# ACT01_RS232_V3_0.net
KiCad netlist of a schematic drawn in Altium Designer
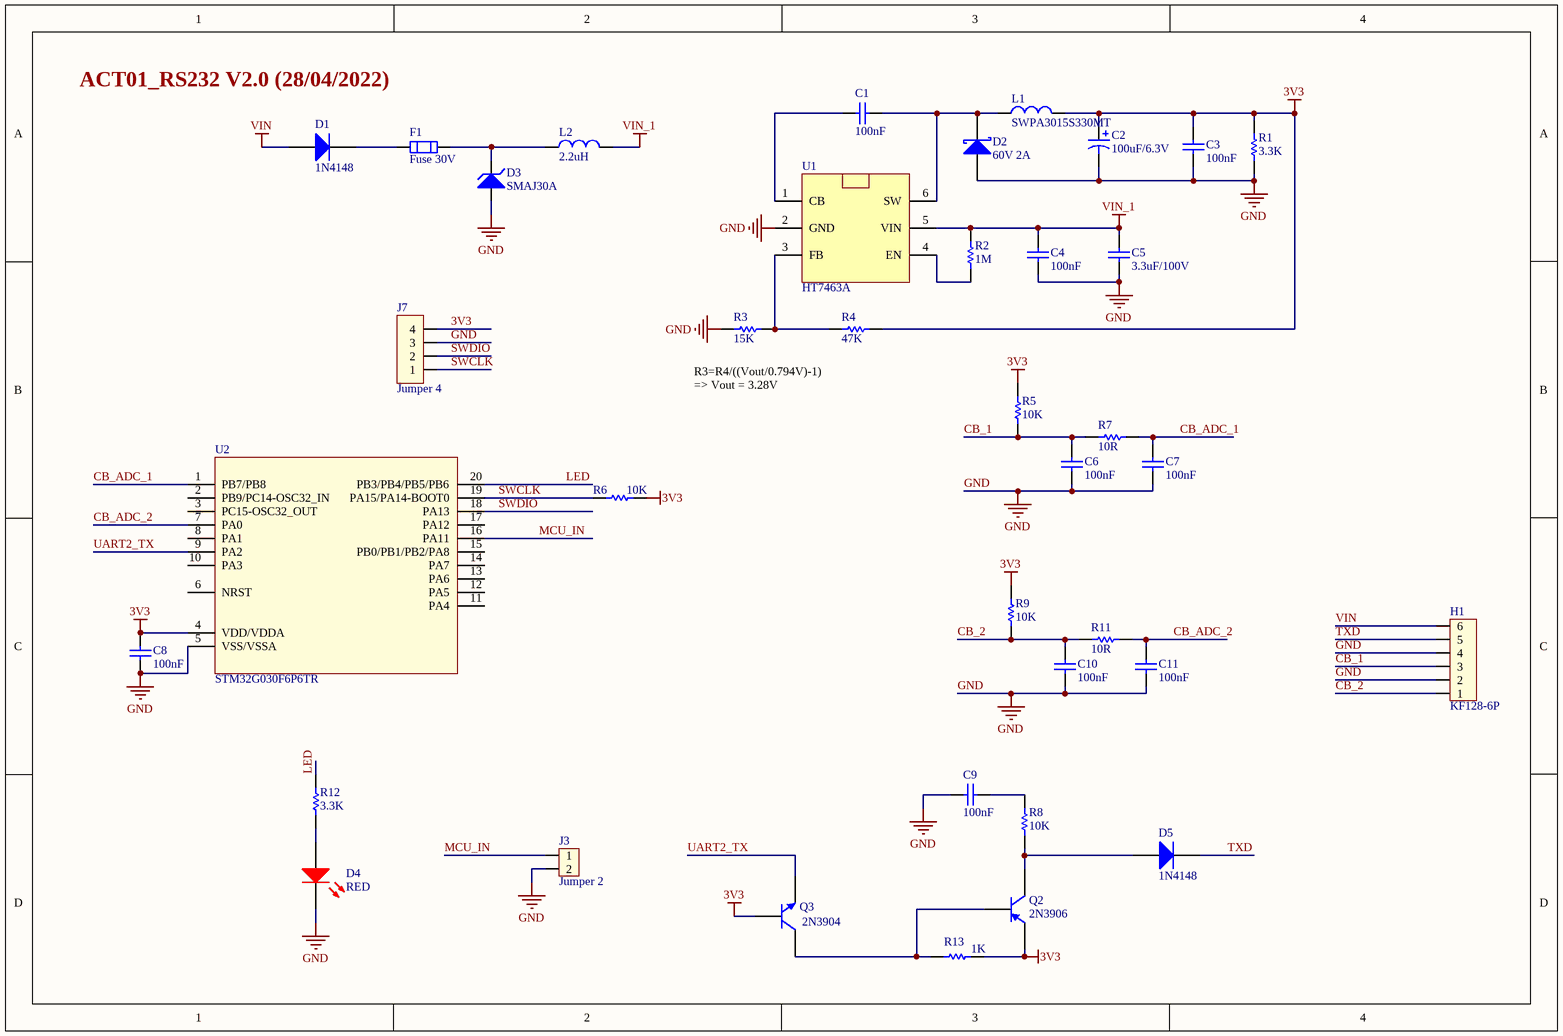
[diagram p0: ACT01_RS232 V3.0.SchDoc]

(export (version "E")
  (design (tool "Eeschema 10.0.6"))
  (components
    (comp (ref "C1")
      (value "100nF")
      (footprint "0603 - C")
      (description "CAP CER 100nF 50V C0G/NP0 0603")
      (fields (field (name "MPN") "CL10C104JB8NNNC") (field (name "MFR") "SAMSUNG"))
      (libsource (lib "Library_Chip1") (part "Cap 0603 100nF"))
    )
    (comp (ref "C2")
      (value "100uF/6.3V")
      (footprint "3528 - TANTALUM")
      (description "CAP TANT 100UF 6.3V 10% 1411")
      (fields (field (name "MPN") "T491B107K006AT") (field (name "MFR") "Kemet"))
      (libsource (lib "Library_Chip1") (part "Cap Tan 3528 100uF/6.3V"))
    )
    (comp (ref "C3")
      (value "100nF")
      (footprint "0603 - C")
      (description "CAP CER 100nF 50V C0G/NP0 0603")
      (fields (field (name "MPN") "CL10C104JB8NNNC") (field (name "MFR") "SAMSUNG"))
      (libsource (lib "Library_Chip1") (part "Cap 0603 100nF"))
    )
    (comp (ref "C4")
      (value "100nF")
      (footprint "0603 - C")
      (description "CAP CER 100nF 50V C0G/NP0 0603")
      (fields (field (name "MPN") "CL10C104JB8NNNC") (field (name "MFR") "SAMSUNG"))
      (libsource (lib "Library_Chip1") (part "Cap 0603 100nF"))
    )
    (comp (ref "C5")
      (value "3.3uF/100V")
      (footprint "1210 - C")
      (description "CAP CER 3.3UF 100V X7S 1210")
      (fields (field (name "MPN") "C3225X7S2A335M200AB") (field (name "MFR") "TDK Corporation"))
      (libsource (lib "Library_Chip1") (part "Cap 1210 3.3uF"))
    )
    (comp (ref "C6")
      (value "100nF")
      (footprint "0603 - C")
      (description "CAP CER 100nF 50V C0G/NP0 0603")
      (fields (field (name "MPN") "CL10C104JB8NNNC") (field (name "MFR") "SAMSUNG"))
      (libsource (lib "Library_Chip1") (part "Cap 0603 100nF"))
    )
    (comp (ref "C7")
      (value "100nF")
      (footprint "0603 - C")
      (description "CAP CER 100nF 50V C0G/NP0 0603")
      (fields (field (name "MPN") "CL10C104JB8NNNC") (field (name "MFR") "SAMSUNG"))
      (libsource (lib "Library_Chip1") (part "Cap 0603 100nF"))
    )
    (comp (ref "C8")
      (value "100nF")
      (footprint "0603 - C")
      (description "CAP CER 100nF 50V C0G/NP0 0603")
      (fields (field (name "MPN") "CL10C104JB8NNNC") (field (name "MFR") "SAMSUNG"))
      (libsource (lib "Library_Chip") (part "Cap 0603 100nF"))
    )
    (comp (ref "C9")
      (value "100nF")
      (footprint "0603 - C")
      (description "CAP CER 100nF 50V C0G/NP0 0603")
      (fields (field (name "MPN") "CL10C104JB8NNNC") (field (name "MFR") "SAMSUNG"))
      (libsource (lib "Library_Chip") (part "Cap 0603 100nF"))
    )
    (comp (ref "C10")
      (value "100nF")
      (footprint "0603 - C")
      (description "CAP CER 100nF 50V C0G/NP0 0603")
      (fields (field (name "MPN") "CL10C104JB8NNNC") (field (name "MFR") "SAMSUNG"))
      (libsource (lib "Library_Chip1") (part "Cap 0603 100nF"))
    )
    (comp (ref "C11")
      (value "100nF")
      (footprint "0603 - C")
      (description "CAP CER 100nF 50V C0G/NP0 0603")
      (fields (field (name "MPN") "CL10C104JB8NNNC") (field (name "MFR") "SAMSUNG"))
      (libsource (lib "Library_Chip1") (part "Cap 0603 100nF"))
    )
    (comp (ref "D1")
      (value "1N4148")
      (footprint "SOD-123")
      (description "DIODE GEN PURP 100V 300MA SOD123")
      (fields (field (name "MPN") "1N4148W-7-F") (field (name "MFR") "DIODES"))
      (libsource (lib "Library_Chip") (part "Diode 1N4148"))
    )
    (comp (ref "D2")
      (value "60V 2A")
      (footprint "SOD-123")
      (description "DIODE SCHOTTKY 60V 2A SOD123W")
      (fields (field (name "MPN") "PMEG6020ER,115") (field (name "MFR") "NXP"))
      (libsource (lib "Library_Chip") (part "Diode PMEG6020ER"))
    )
    (comp (ref "D3")
      (value "SMAJ30A")
      (footprint "Diode - SMA")
      (description "TVS DIODE 30V 48.4V DO214AC")
      (fields (field (name "MFR") "Littelfuse Inc."))
      (libsource (lib "Library_Chip") (part "Diode SMAJ30A"))
    )
    (comp (ref "D4")
      (value "RED")
      (footprint "LED - 0603 - R")
      (description "LED RED CLEAR 0603 SMD")
      (fields (field (name "MFR") "Everlight") (field (name "MPN") "QTLP601CRTR"))
      (libsource (lib "Library_Chip") (part "LED 0603 RED"))
    )
    (comp (ref "D5")
      (value "1N4148")
      (footprint "SOD-123")
      (description "DIODE GEN PURP 100V 300MA SOD123")
      (fields (field (name "MPN") "1N4148W-7-F") (field (name "MFR") "DIODES"))
      (libsource (lib "Library_Chip") (part "Diode 1N4148"))
    )
    (comp (ref "F1")
      (value "Fuse 30V")
      (footprint "1206 - Fuse")
      (description "PTC RESET FUSE 30V 0.125A 1206")
      (fields (field (name "MFR") "BrightKing") (field (name "MPN") "SMD1206B012TF"))
      (libsource (lib "Library_Chip") (part "Fuse 30V - 0.125A"))
    )
    (comp (ref "H1")
      (value "KF128-6P")
      (footprint "KF128 - 6P")
      (description "6-Pin Plug-in Terminal Block Connector 5.08mm Pitch Through Hole")
      (fields (field (name "MPN") "KF128 - 6P") (field (name "MFR") "China"))
      (libsource (lib "Library_ Connector") (part "HD KF128 6P"))
    )
    (comp (ref "J3")
      (value "Jumper 2")
      (footprint "JP2")
      (description "Jumper 2, 2.54mmx2")
      (libsource (lib "Library_ Connector") (part "JP2"))
    )
    (comp (ref "J7")
      (value "Jumper 4")
      (footprint "JP4 2mm")
      (description "Jumper 4, 2.54mmx4")
      (libsource (lib "Library_ Connector") (part "JP4"))
    )
    (comp (ref "L1")
      (value "SWPA3015S330MT")
      (footprint "IND_3x3")
      (description "FIXED IND 33UH 430MA 1.066OHM SM")
      (fields (field (name "MFR") "Shenzhen Sunlord Electronics Co., Ltd."))
      (libsource (lib "Library_Chip") (part "Inductor 33uH"))
    )
    (comp (ref "L2")
      (value "2.2uH")
      (footprint "1210 - L")
      (description "FIXED IND 2.2UH 1.6A 76 MOHM SMD")
      (fields (field (name "MPN") "LQH32PN2R2NN0") (field (name "MFR") "Murata"))
      (libsource (lib "Library_Chip") (part "Inductor 3225 2.2uH"))
    )
    (comp (ref "Q2")
      (value "2N3906")
      (footprint "SOT23B")
      (description "TRANS PNP 40V 0.2A SOT23")
      (fields (field (name "MPN") "MMBT3906") (field (name "MFR") "Fairchild"))
      (libsource (lib "Library_Chip") (part "Transistor 2N3906"))
    )
    (comp (ref "Q3")
      (value "2N3904")
      (footprint "SOT23B")
      (description "TRANS NPN 40V 0.2A SOT-23")
      (fields (field (name "MPN") "MMBT3904") (field (name "MFR") "Fairchild"))
      (libsource (lib "Library_Chip") (part "Transistor 2N3904"))
    )
    (comp (ref "R1")
      (value "3.3K")
      (footprint "0603 - R")
      (description "RES SMD 3.3K OHM 1% 1/10W 0603")
      (fields (field (name "MFR") "Yageo") (field (name "MPN") "RC0603FR-073K3L"))
      (libsource (lib "Library_Chip") (part "Res 0603 3.3K"))
    )
    (comp (ref "R2")
      (value "1M")
      (footprint "0603 - R")
      (description "RES SMD 1M OHM 1% 1/10W 0603")
      (fields (field (name "MFR") "Yageo") (field (name "MPN") "RC0603FR-071ML"))
      (libsource (lib "Library_Chip1") (part "Res 0603 1M"))
    )
    (comp (ref "R3")
      (value "15K")
      (footprint "0603 - R")
      (description "RES SMD 15K OHM 1% 1/10W 0603")
      (fields (field (name "MFR") "Yageo") (field (name "MPN") "RC0603FR-0715KL"))
      (libsource (lib "Library_Chip1") (part "Res 0603 15K"))
    )
    (comp (ref "R4")
      (value "47K")
      (footprint "0603 - R")
      (description "RES SMD 47K OHM 1% 1/10W 0603")
      (fields (field (name "MFR") "Yageo") (field (name "MPN") "RE0603FRE0747KL"))
      (libsource (lib "Library_Chip1") (part "Res 0603 47K"))
    )
    (comp (ref "R5")
      (value "10K")
      (footprint "0603 - R")
      (description "RES SMD 10K OHM 1% 1/10W 0603")
      (fields (field (name "MFR") "Yageo") (field (name "MPN") "RC0603FR-0710KL"))
      (libsource (lib "Library_Chip") (part "Res 0603 10K"))
    )
    (comp (ref "R6")
      (value "10K")
      (footprint "0603 - R")
      (description "RES SMD 10K OHM 1% 1/10W 0603")
      (fields (field (name "MFR") "Yageo") (field (name "MPN") "RC0603FR-0710KL"))
      (libsource (lib "Library_Chip") (part "Res 0603 10K"))
    )
    (comp (ref "R7")
      (value "10R")
      (footprint "0603 - R")
      (description "RES SMD 10 OHM 1% 1/10W 0603")
      (fields (field (name "MFR") "Yageo") (field (name "MPN") "RC0603FR-0710RL"))
      (libsource (lib "Library_Chip") (part "Res 0603 10R"))
    )
    (comp (ref "R8")
      (value "10K")
      (footprint "0603 - R")
      (description "RES SMD 10K OHM 1% 1/10W 0603")
      (fields (field (name "MFR") "Yageo") (field (name "MPN") "RC0603FR-0710KL"))
      (libsource (lib "Library_Chip") (part "Res 0603 10K"))
    )
    (comp (ref "R9")
      (value "10K")
      (footprint "0603 - R")
      (description "RES SMD 10K OHM 1% 1/10W 0603")
      (fields (field (name "MFR") "Yageo") (field (name "MPN") "RC0603FR-0710KL"))
      (libsource (lib "Library_Chip") (part "Res 0603 10K"))
    )
    (comp (ref "R11")
      (value "10R")
      (footprint "0603 - R")
      (description "RES SMD 10 OHM 1% 1/10W 0603")
      (fields (field (name "MFR") "Yageo") (field (name "MPN") "RC0603FR-0710RL"))
      (libsource (lib "Library_Chip") (part "Res 0603 10R"))
    )
    (comp (ref "R12")
      (value "3.3K")
      (footprint "0603 - R")
      (description "RES SMD 3.3K OHM 1% 1/10W 0603")
      (fields (field (name "MFR") "Yageo") (field (name "MPN") "RC0603FR-073K3L"))
      (libsource (lib "Library_Chip") (part "Res 0603 3.3K"))
    )
    (comp (ref "R13")
      (value "1K")
      (footprint "0603 - R")
      (description "RES SMD 1K OHM 1% 1/10W 0603")
      (fields (field (name "MFR") "Yageo") (field (name "MPN") "RC0603FR-071KL"))
      (libsource (lib "Library_Chip") (part "Res 0603 1K"))
    )
    (comp (ref "U1")
      (value "HT7463A")
      (footprint "SOT23-6_L")
      (description "52V/600mA, 1.25MHz/550kHz\r\nAsynchronous Step Down Converter")
      (fields (field (name "MFR") "Holtek"))
      (libsource (lib "Library_IC") (part "HT7463A/HT7463B"))
    )
    (comp (ref "U2")
      (value "STM32G030F6P6TR")
      (footprint "TSSOP20")
      (description "IC MCU 32BIT 32KB FLASH 20TSSOP")
      (fields (field (name "MPN") "STMicroelectronics"))
      (libsource (lib "Library_IC") (part "STM32G030F6P6TR"))
    )
  )
  (nets
    (net (code "1") (name "/CB_1") (class "Default")
      (node (ref "C6") (pin "2") (pinfunction "2_2") (pintype "passive"))
      (node (ref "H1") (pin "3") (pinfunction "3_3") (pintype "passive"))
      (node (ref "R5") (pin "1") (pinfunction "1_1") (pintype "passive"))
      (node (ref "R7") (pin "1") (pinfunction "1_1") (pintype "passive"))
    )
    (net (code "2") (name "/CB_2") (class "Default")
      (node (ref "C10") (pin "2") (pinfunction "2_2") (pintype "passive"))
      (node (ref "H1") (pin "1") (pinfunction "1_1") (pintype "passive"))
      (node (ref "R11") (pin "1") (pinfunction "1_1") (pintype "passive"))
      (node (ref "R9") (pin "1") (pinfunction "1_1") (pintype "passive"))
    )
    (net (code "3") (name "/CB_ADC_1") (class "Default")
      (node (ref "C7") (pin "2") (pinfunction "2_2") (pintype "passive"))
      (node (ref "R7") (pin "2") (pinfunction "2_2") (pintype "passive"))
      (node (ref "U2") (pin "1") (pinfunction "PB7/PB8_1") (pintype "power_in"))
    )
    (net (code "4") (name "/CB_ADC_2") (class "Default")
      (node (ref "C11") (pin "2") (pinfunction "2_2") (pintype "passive"))
      (node (ref "R11") (pin "2") (pinfunction "2_2") (pintype "passive"))
      (node (ref "U2") (pin "7") (pinfunction "PA0_7") (pintype "power_in"))
    )
    (net (code "5") (name "/LED") (class "Default")
      (node (ref "R12") (pin "2") (pinfunction "2_2") (pintype "passive"))
      (node (ref "U2") (pin "20") (pinfunction "PB3/PB4/PB5/PB6_20") (pintype "power_in"))
    )
    (net (code "6") (name "/MCU_IN") (class "Default")
      (node (ref "J3") (pin "1") (pinfunction "1_1") (pintype "passive"))
      (node (ref "U2") (pin "16") (pinfunction "PA11_16") (pintype "power_in"))
    )
    (net (code "7") (name "/SWCLK") (class "Default")
      (node (ref "J7") (pin "1") (pinfunction "1_1") (pintype "passive"))
      (node (ref "R6") (pin "1") (pinfunction "1_1") (pintype "passive"))
      (node (ref "U2") (pin "19") (pinfunction "PA15/PA14-BOOT0_19") (pintype "power_in"))
    )
    (net (code "8") (name "/SWDIO") (class "Default")
      (node (ref "J7") (pin "2") (pinfunction "2_2") (pintype "passive"))
      (node (ref "U2") (pin "18") (pinfunction "PA13_18") (pintype "power_in"))
    )
    (net (code "9") (name "/TXD") (class "Default")
      (node (ref "D5") (pin "2") (pinfunction "K_2") (pintype "passive"))
      (node (ref "H1") (pin "5") (pinfunction "5_5") (pintype "passive"))
    )
    (net (code "10") (name "/UART2_TX") (class "Default")
      (node (ref "Q3") (pin "2") (pinfunction "E_2") (pintype "passive"))
      (node (ref "U2") (pin "9") (pinfunction "PA2_9") (pintype "power_in"))
    )
    (net (code "11") (name "3V3") (class "Default")
      (node (ref "C2") (pin "1") (pinfunction "1_1") (pintype "passive"))
      (node (ref "C3") (pin "2") (pinfunction "2_2") (pintype "passive"))
      (node (ref "C8") (pin "2") (pinfunction "2_2") (pintype "passive"))
      (node (ref "J7") (pin "4") (pinfunction "4_4") (pintype "passive"))
      (node (ref "L1") (pin "2") (pinfunction "2_2") (pintype "passive"))
      (node (ref "Q2") (pin "2") (pinfunction "E_2") (pintype "passive"))
      (node (ref "Q3") (pin "1") (pinfunction "B_1") (pintype "passive"))
      (node (ref "R1") (pin "2") (pinfunction "2_2") (pintype "passive"))
      (node (ref "R13") (pin "2") (pinfunction "2_2") (pintype "passive"))
      (node (ref "R4") (pin "2") (pinfunction "2_2") (pintype "passive"))
      (node (ref "R5") (pin "2") (pinfunction "2_2") (pintype "passive"))
      (node (ref "R6") (pin "2") (pinfunction "2_2") (pintype "passive"))
      (node (ref "R9") (pin "2") (pinfunction "2_2") (pintype "passive"))
      (node (ref "U2") (pin "4") (pinfunction "VDD/VDDA_4") (pintype "power_in"))
    )
    (net (code "12") (name "GND") (class "Default")
      (node (ref "C10") (pin "1") (pinfunction "1_1") (pintype "passive"))
      (node (ref "C11") (pin "1") (pinfunction "1_1") (pintype "passive"))
      (node (ref "C2") (pin "2") (pinfunction "2_2") (pintype "passive"))
      (node (ref "C3") (pin "1") (pinfunction "1_1") (pintype "passive"))
      (node (ref "C4") (pin "1") (pinfunction "1_1") (pintype "passive"))
      (node (ref "C5") (pin "1") (pinfunction "1_1") (pintype "passive"))
      (node (ref "C6") (pin "1") (pinfunction "1_1") (pintype "passive"))
      (node (ref "C7") (pin "1") (pinfunction "1_1") (pintype "passive"))
      (node (ref "C8") (pin "1") (pinfunction "1_1") (pintype "passive"))
      (node (ref "C9") (pin "1") (pinfunction "1_1") (pintype "passive"))
      (node (ref "D2") (pin "1") (pinfunction "A_1") (pintype "passive"))
      (node (ref "D3") (pin "1") (pinfunction "A_1") (pintype "passive"))
      (node (ref "D4") (pin "2") (pinfunction "K_2") (pintype "passive"))
      (node (ref "H1") (pin "2") (pinfunction "2_2") (pintype "passive"))
      (node (ref "H1") (pin "4") (pinfunction "4_4") (pintype "passive"))
      (node (ref "J3") (pin "2") (pinfunction "2_2") (pintype "passive"))
      (node (ref "J7") (pin "3") (pinfunction "3_3") (pintype "passive"))
      (node (ref "R1") (pin "1") (pinfunction "1_1") (pintype "passive"))
      (node (ref "R3") (pin "2") (pinfunction "2_2") (pintype "passive"))
      (node (ref "U1") (pin "2") (pinfunction "GND_2") (pintype "power_in"))
      (node (ref "U2") (pin "5") (pinfunction "VSS/VSSA_5") (pintype "power_in"))
    )
    (net (code "13") (name "Net-(C9-Pad2)") (class "Default")
      (node (ref "C9") (pin "2") (pinfunction "2_2") (pintype "passive"))
      (node (ref "R8") (pin "1") (pinfunction "1_1") (pintype "passive"))
    )
    (net (code "14") (name "Net-(D1-K)") (class "Default")
      (node (ref "D1") (pin "2") (pinfunction "K_2") (pintype "passive"))
      (node (ref "F1") (pin "1") (pinfunction "1_1") (pintype "passive"))
    )
    (net (code "15") (name "Net-(D2-K)") (class "Default")
      (node (ref "C1") (pin "2") (pinfunction "2_2") (pintype "passive"))
      (node (ref "D2") (pin "2") (pinfunction "K_2") (pintype "passive"))
      (node (ref "L1") (pin "1") (pinfunction "1_1") (pintype "passive"))
      (node (ref "U1") (pin "6") (pinfunction "SW_6") (pintype "power_in"))
    )
    (net (code "16") (name "Net-(D3-K)") (class "Default")
      (node (ref "D3") (pin "2") (pinfunction "K_2") (pintype "passive"))
      (node (ref "F1") (pin "2") (pinfunction "2_2") (pintype "passive"))
      (node (ref "L2") (pin "1") (pinfunction "1_1") (pintype "passive"))
    )
    (net (code "17") (name "Net-(D4-A)") (class "Default")
      (node (ref "D4") (pin "1") (pinfunction "A_1") (pintype "passive"))
      (node (ref "R12") (pin "1") (pinfunction "1_1") (pintype "passive"))
    )
    (net (code "18") (name "Net-(D5-A)") (class "Default")
      (node (ref "D5") (pin "1") (pinfunction "A_1") (pintype "passive"))
      (node (ref "Q2") (pin "3") (pinfunction "C_3") (pintype "passive"))
      (node (ref "R8") (pin "2") (pinfunction "2_2") (pintype "passive"))
    )
    (net (code "19") (name "Net-(Q2-B)") (class "Default")
      (node (ref "Q2") (pin "1") (pinfunction "B_1") (pintype "passive"))
      (node (ref "Q3") (pin "3") (pinfunction "C_3") (pintype "passive"))
      (node (ref "R13") (pin "1") (pinfunction "1_1") (pintype "passive"))
    )
    (net (code "20") (name "Net-(U1-CB)") (class "Default")
      (node (ref "C1") (pin "1") (pinfunction "1_1") (pintype "passive"))
      (node (ref "U1") (pin "1") (pinfunction "CB_1") (pintype "power_in"))
    )
    (net (code "21") (name "Net-(U1-EN)") (class "Default")
      (node (ref "R2") (pin "1") (pinfunction "1_1") (pintype "passive"))
      (node (ref "U1") (pin "4") (pinfunction "EN_4") (pintype "power_in"))
    )
    (net (code "22") (name "Net-(U1-FB)") (class "Default")
      (node (ref "R3") (pin "1") (pinfunction "1_1") (pintype "passive"))
      (node (ref "R4") (pin "1") (pinfunction "1_1") (pintype "passive"))
      (node (ref "U1") (pin "3") (pinfunction "FB_3") (pintype "power_in"))
    )
    (net (code "23") (name "VIN") (class "Default")
      (node (ref "D1") (pin "1") (pinfunction "A_1") (pintype "passive"))
      (node (ref "H1") (pin "6") (pinfunction "6_6") (pintype "passive"))
    )
    (net (code "24") (name "VIN_1") (class "Default")
      (node (ref "C4") (pin "2") (pinfunction "2_2") (pintype "passive"))
      (node (ref "C5") (pin "2") (pinfunction "2_2") (pintype "passive"))
      (node (ref "L2") (pin "2") (pinfunction "2_2") (pintype "passive"))
      (node (ref "R2") (pin "2") (pinfunction "2_2") (pintype "passive"))
      (node (ref "U1") (pin "5") (pinfunction "VIN_5") (pintype "power_in"))
    )
    (net (code "25") (name "unconnected-(U2-NRST-Pad6)") (class "Default")
      (node (ref "U2") (pin "6") (pinfunction "NRST_6") (pintype "power_in"))
    )
    (net (code "26") (name "unconnected-(U2-PA1-Pad8)") (class "Default")
      (node (ref "U2") (pin "8") (pinfunction "PA1_8") (pintype "power_in"))
    )
    (net (code "27") (name "unconnected-(U2-PA3-Pad10)") (class "Default")
      (node (ref "U2") (pin "10") (pinfunction "PA3_10") (pintype "power_in"))
    )
    (net (code "28") (name "unconnected-(U2-PA4-Pad11)") (class "Default")
      (node (ref "U2") (pin "11") (pinfunction "PA4_11") (pintype "power_in"))
    )
    (net (code "29") (name "unconnected-(U2-PA5-Pad12)") (class "Default")
      (node (ref "U2") (pin "12") (pinfunction "PA5_12") (pintype "power_in"))
    )
    (net (code "30") (name "unconnected-(U2-PA6-Pad13)") (class "Default")
      (node (ref "U2") (pin "13") (pinfunction "PA6_13") (pintype "power_in"))
    )
    (net (code "31") (name "unconnected-(U2-PA7-Pad14)") (class "Default")
      (node (ref "U2") (pin "14") (pinfunction "PA7_14") (pintype "power_in"))
    )
    (net (code "32") (name "unconnected-(U2-PA12-Pad17)") (class "Default")
      (node (ref "U2") (pin "17") (pinfunction "PA12_17") (pintype "power_in"))
    )
    (net (code "33") (name "unconnected-(U2-PB0{slash}PB1{slash}PB2{slash}PA8-Pad15)") (class "Default")
      (node (ref "U2") (pin "15") (pinfunction "PB0/PB1/PB2/PA8_15") (pintype "power_in"))
    )
    (net (code "34") (name "unconnected-(U2-PB9{slash}PC14-OSC32_IN-Pad2)") (class "Default")
      (node (ref "U2") (pin "2") (pinfunction "PB9/PC14-OSC32_IN_2") (pintype "power_in"))
    )
    (net (code "35") (name "unconnected-(U2-PC15-OSC32_OUT-Pad3)") (class "Default")
      (node (ref "U2") (pin "3") (pinfunction "PC15-OSC32_OUT_3") (pintype "power_in"))
    )
  )
)
